# mrShark_11.net
KiCad netlist of a schematic drawn in EAGLE
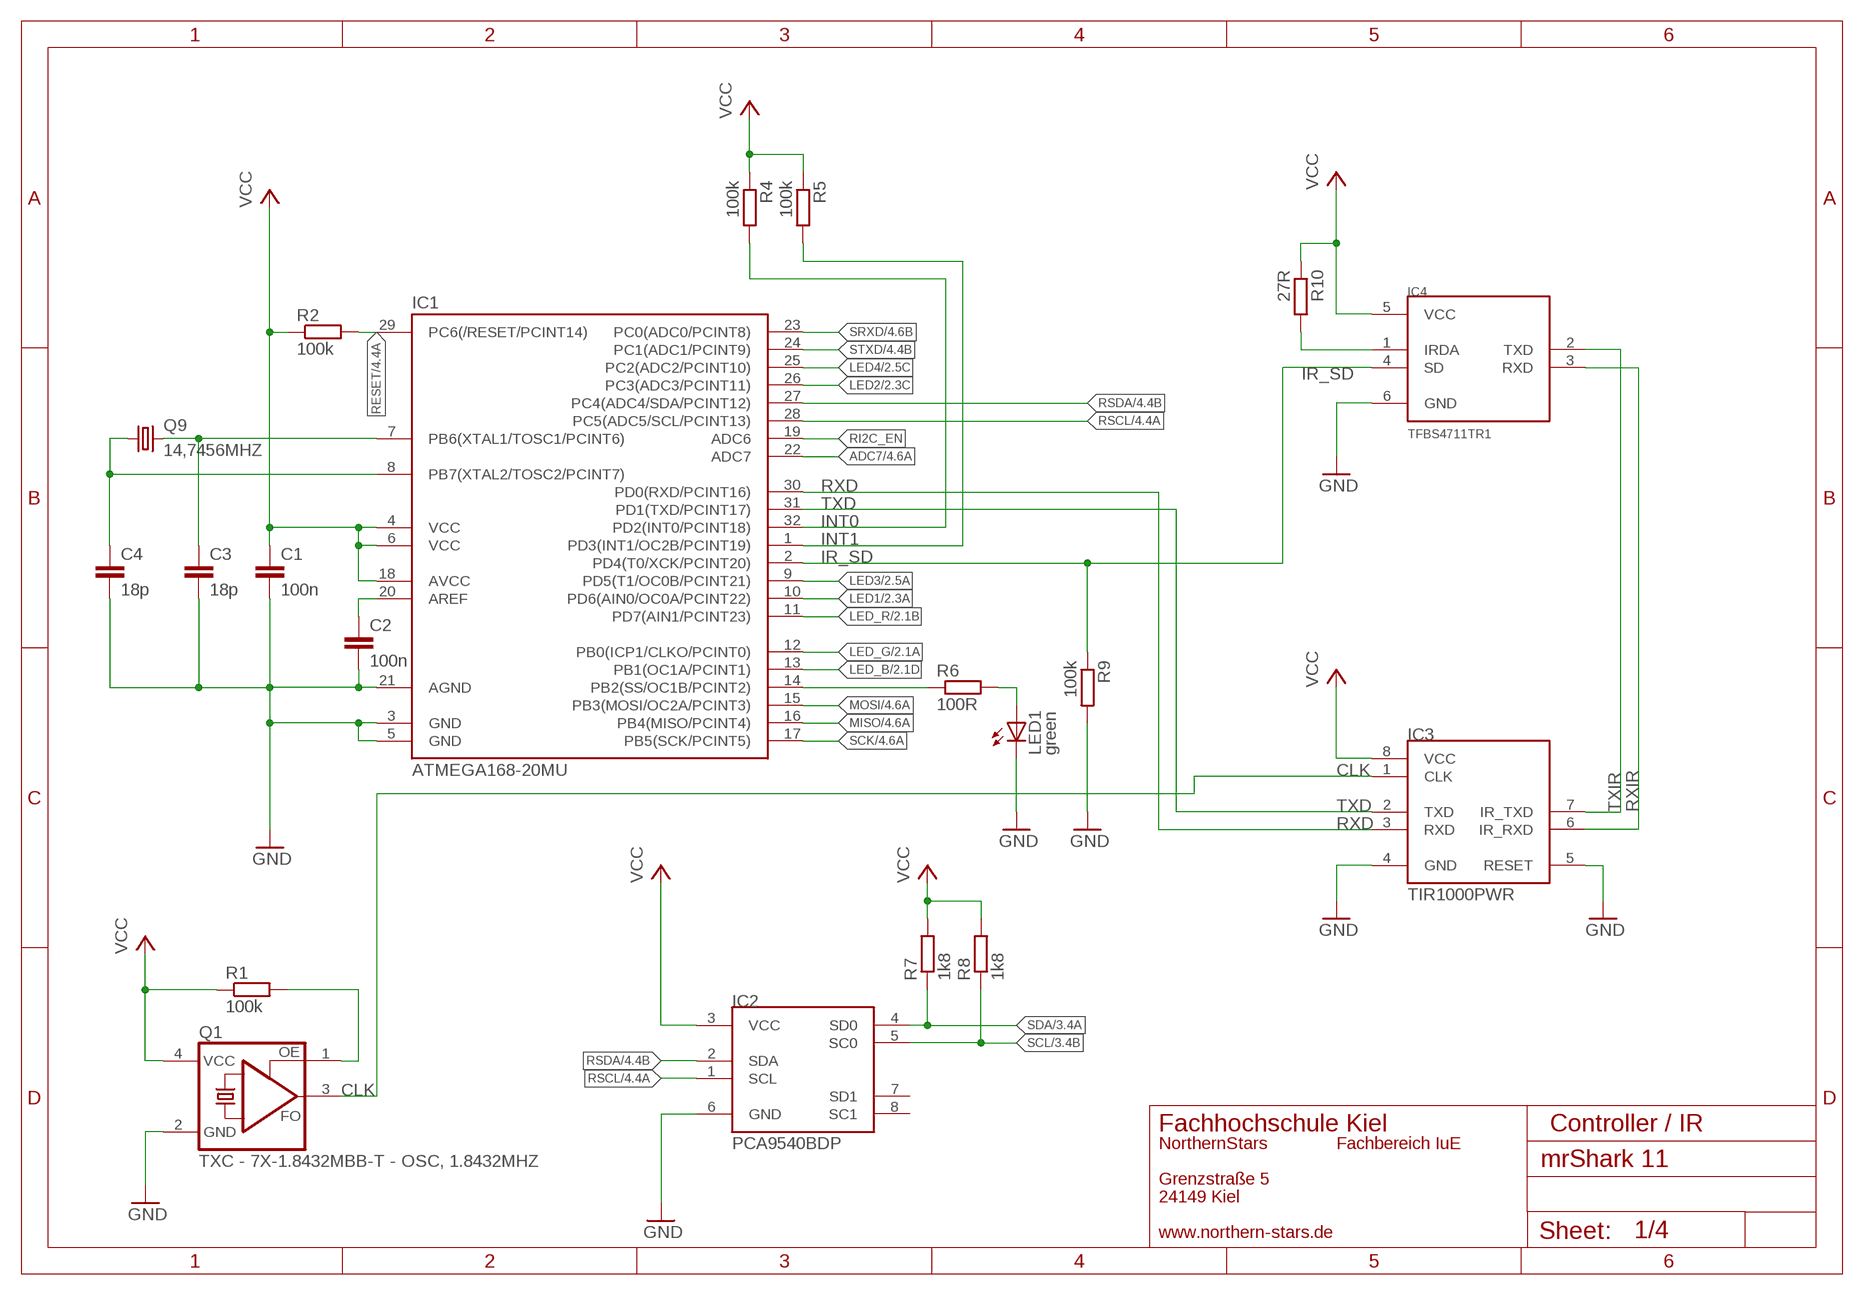
[diagram p0: schematic, sheet 1]
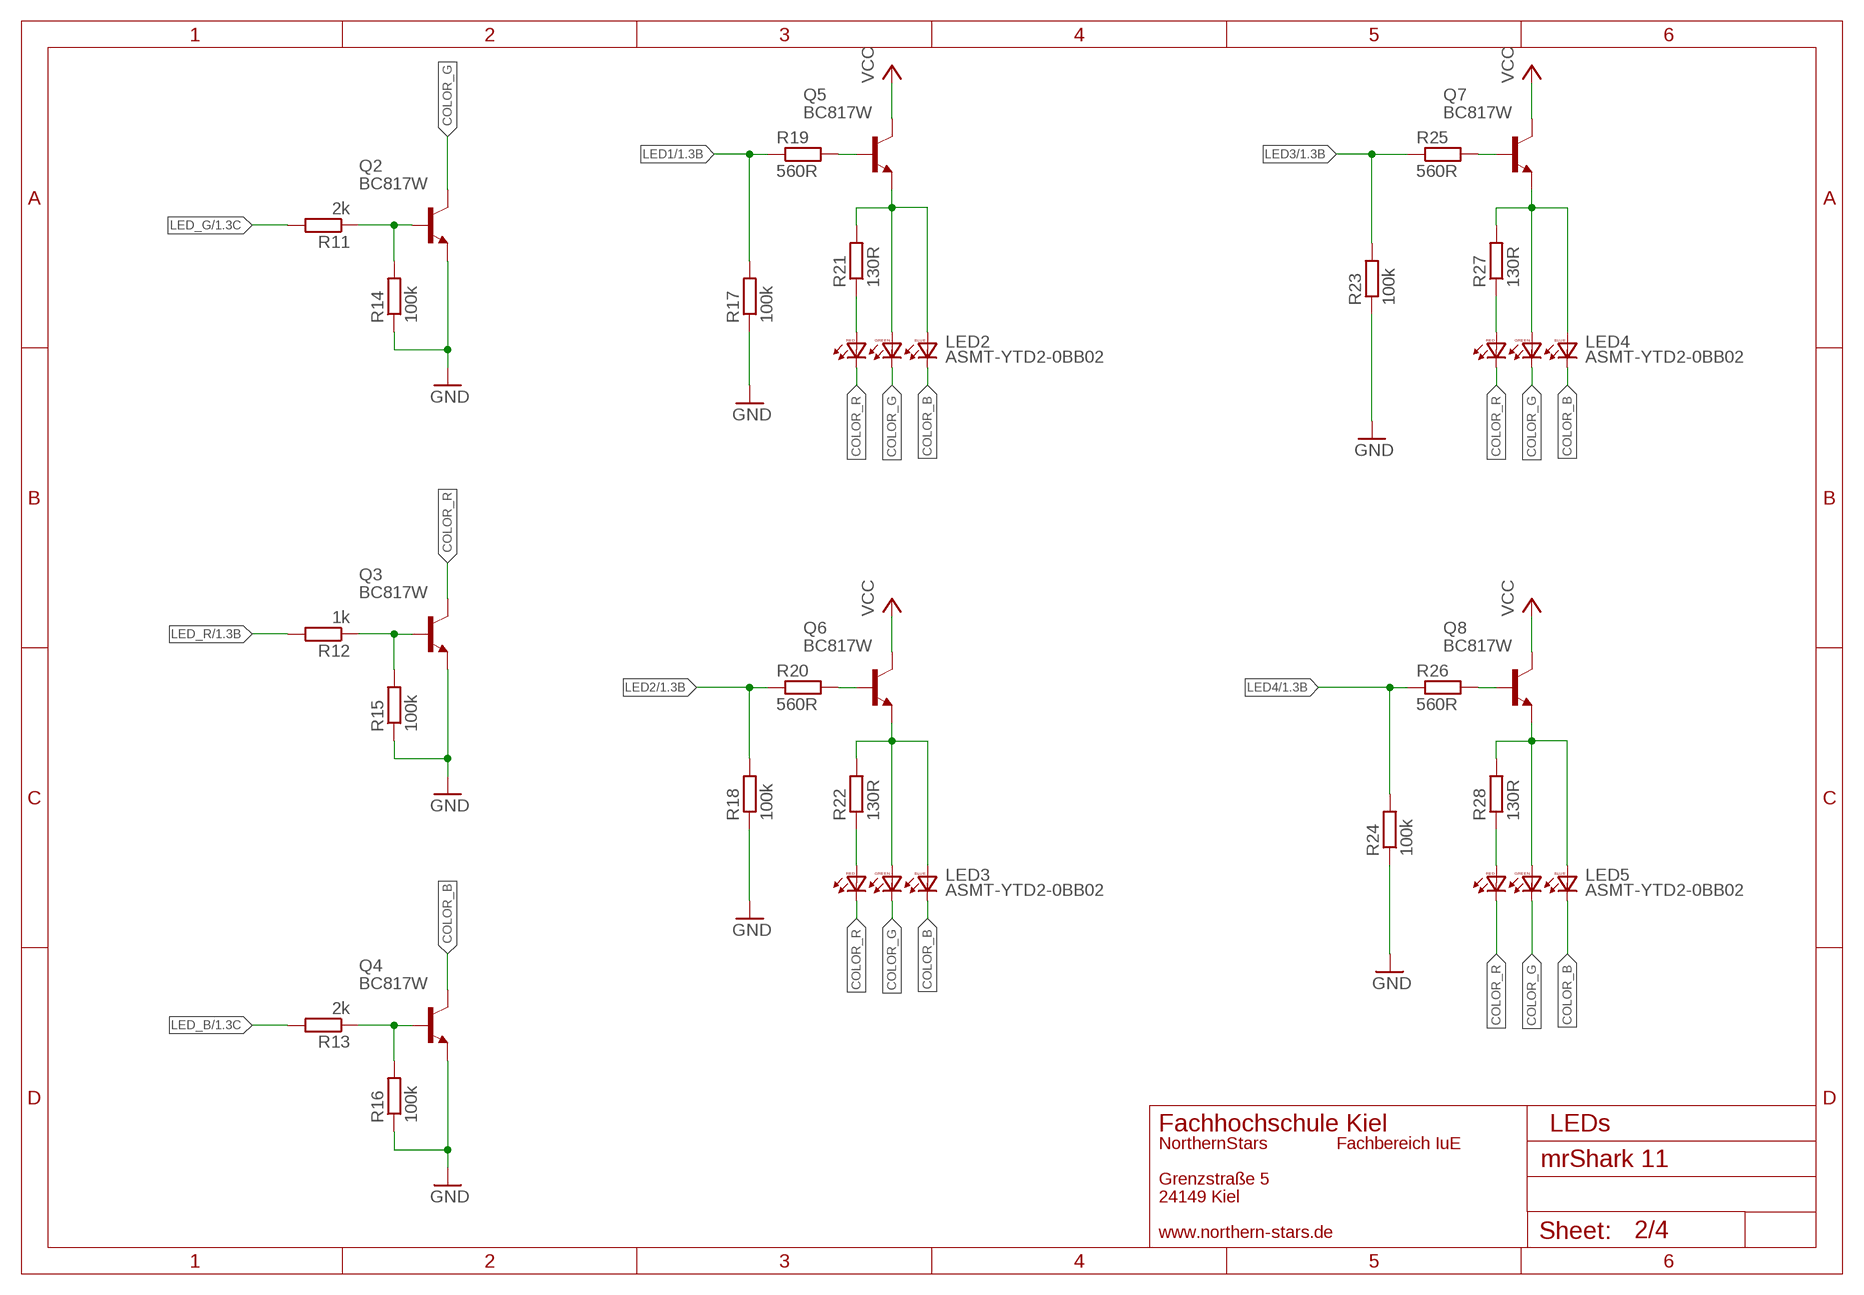
[diagram p1: schematic, sheet 2]
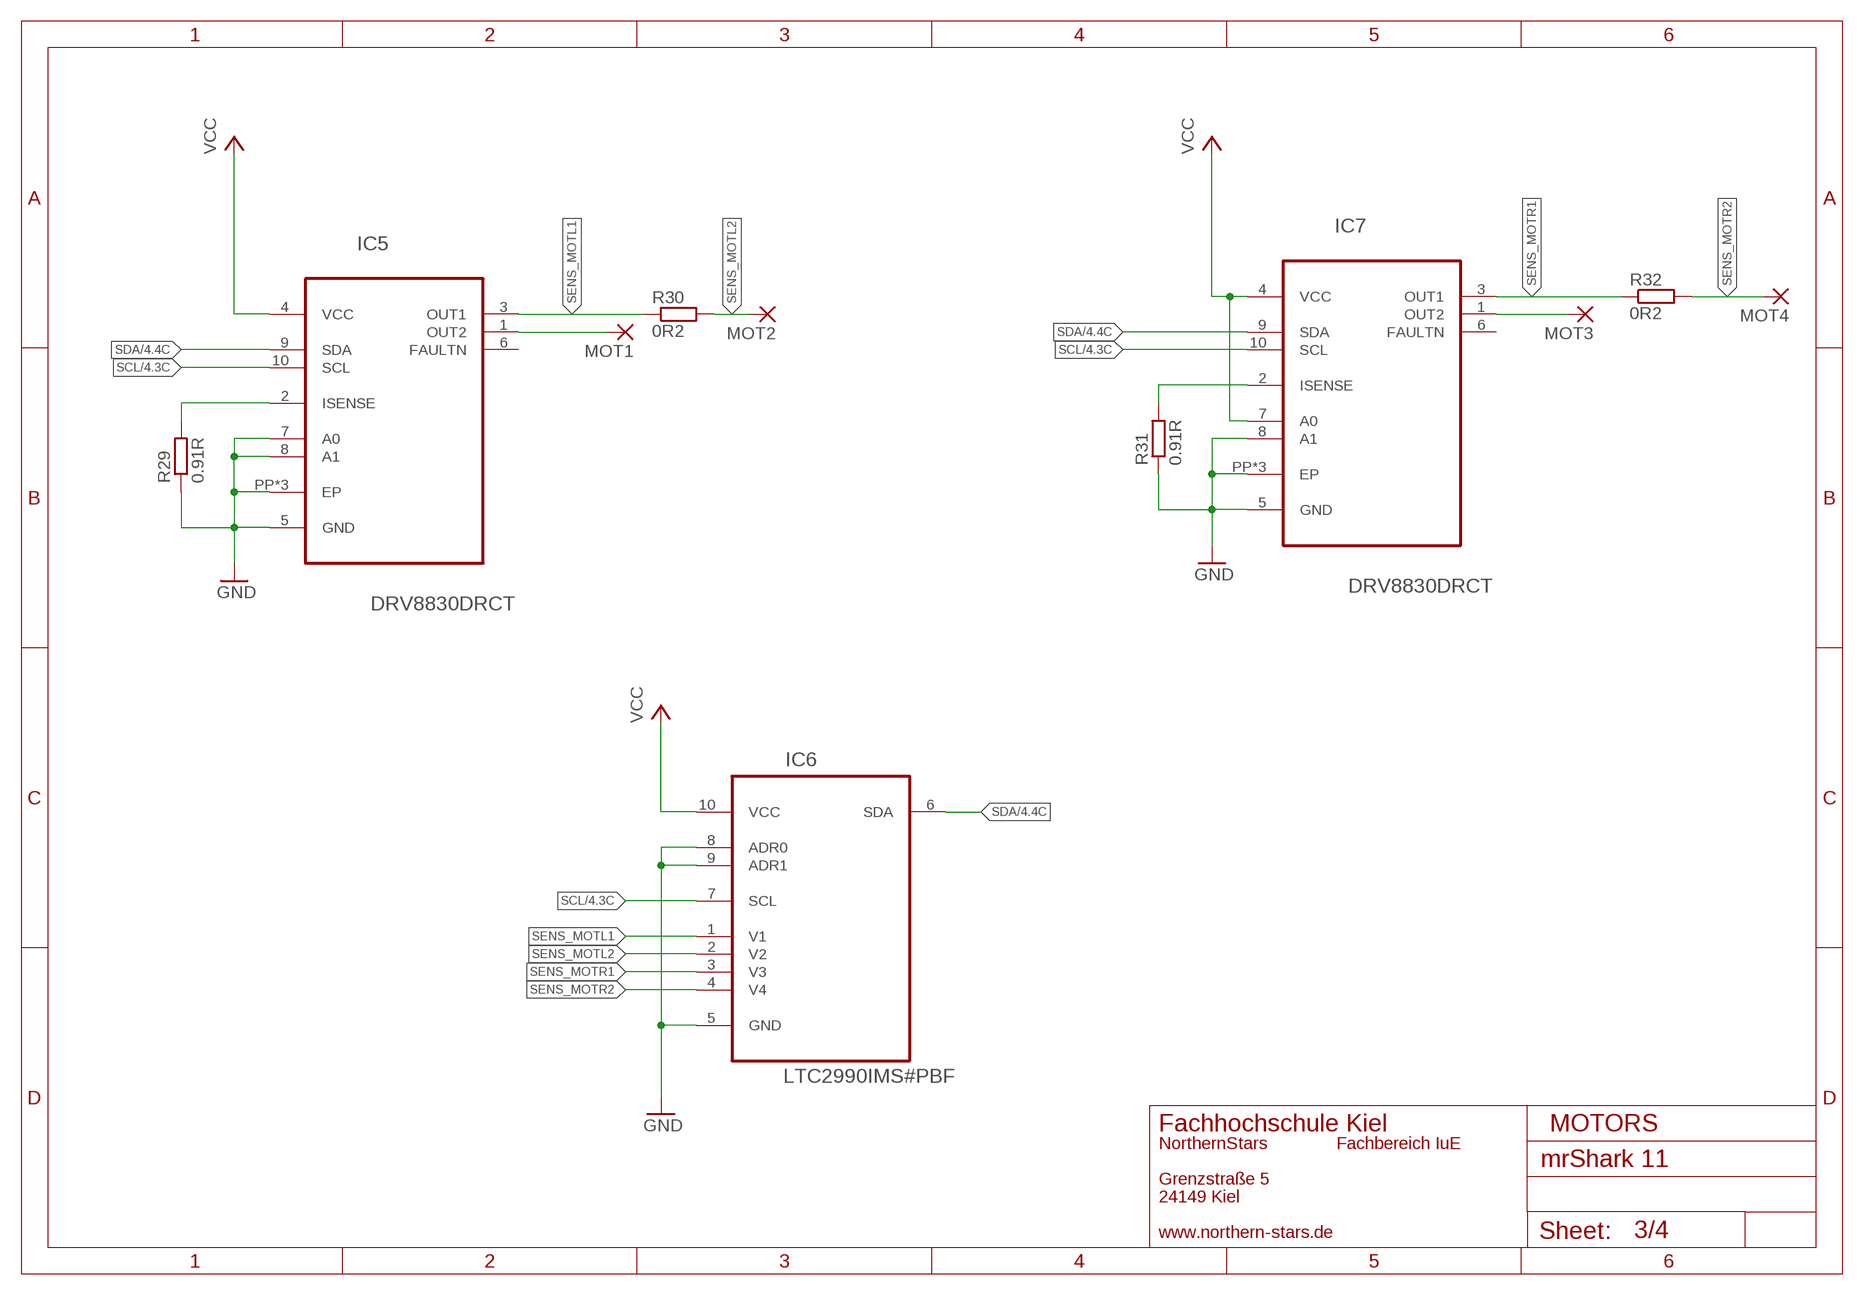
[diagram p2: schematic, sheet 3]
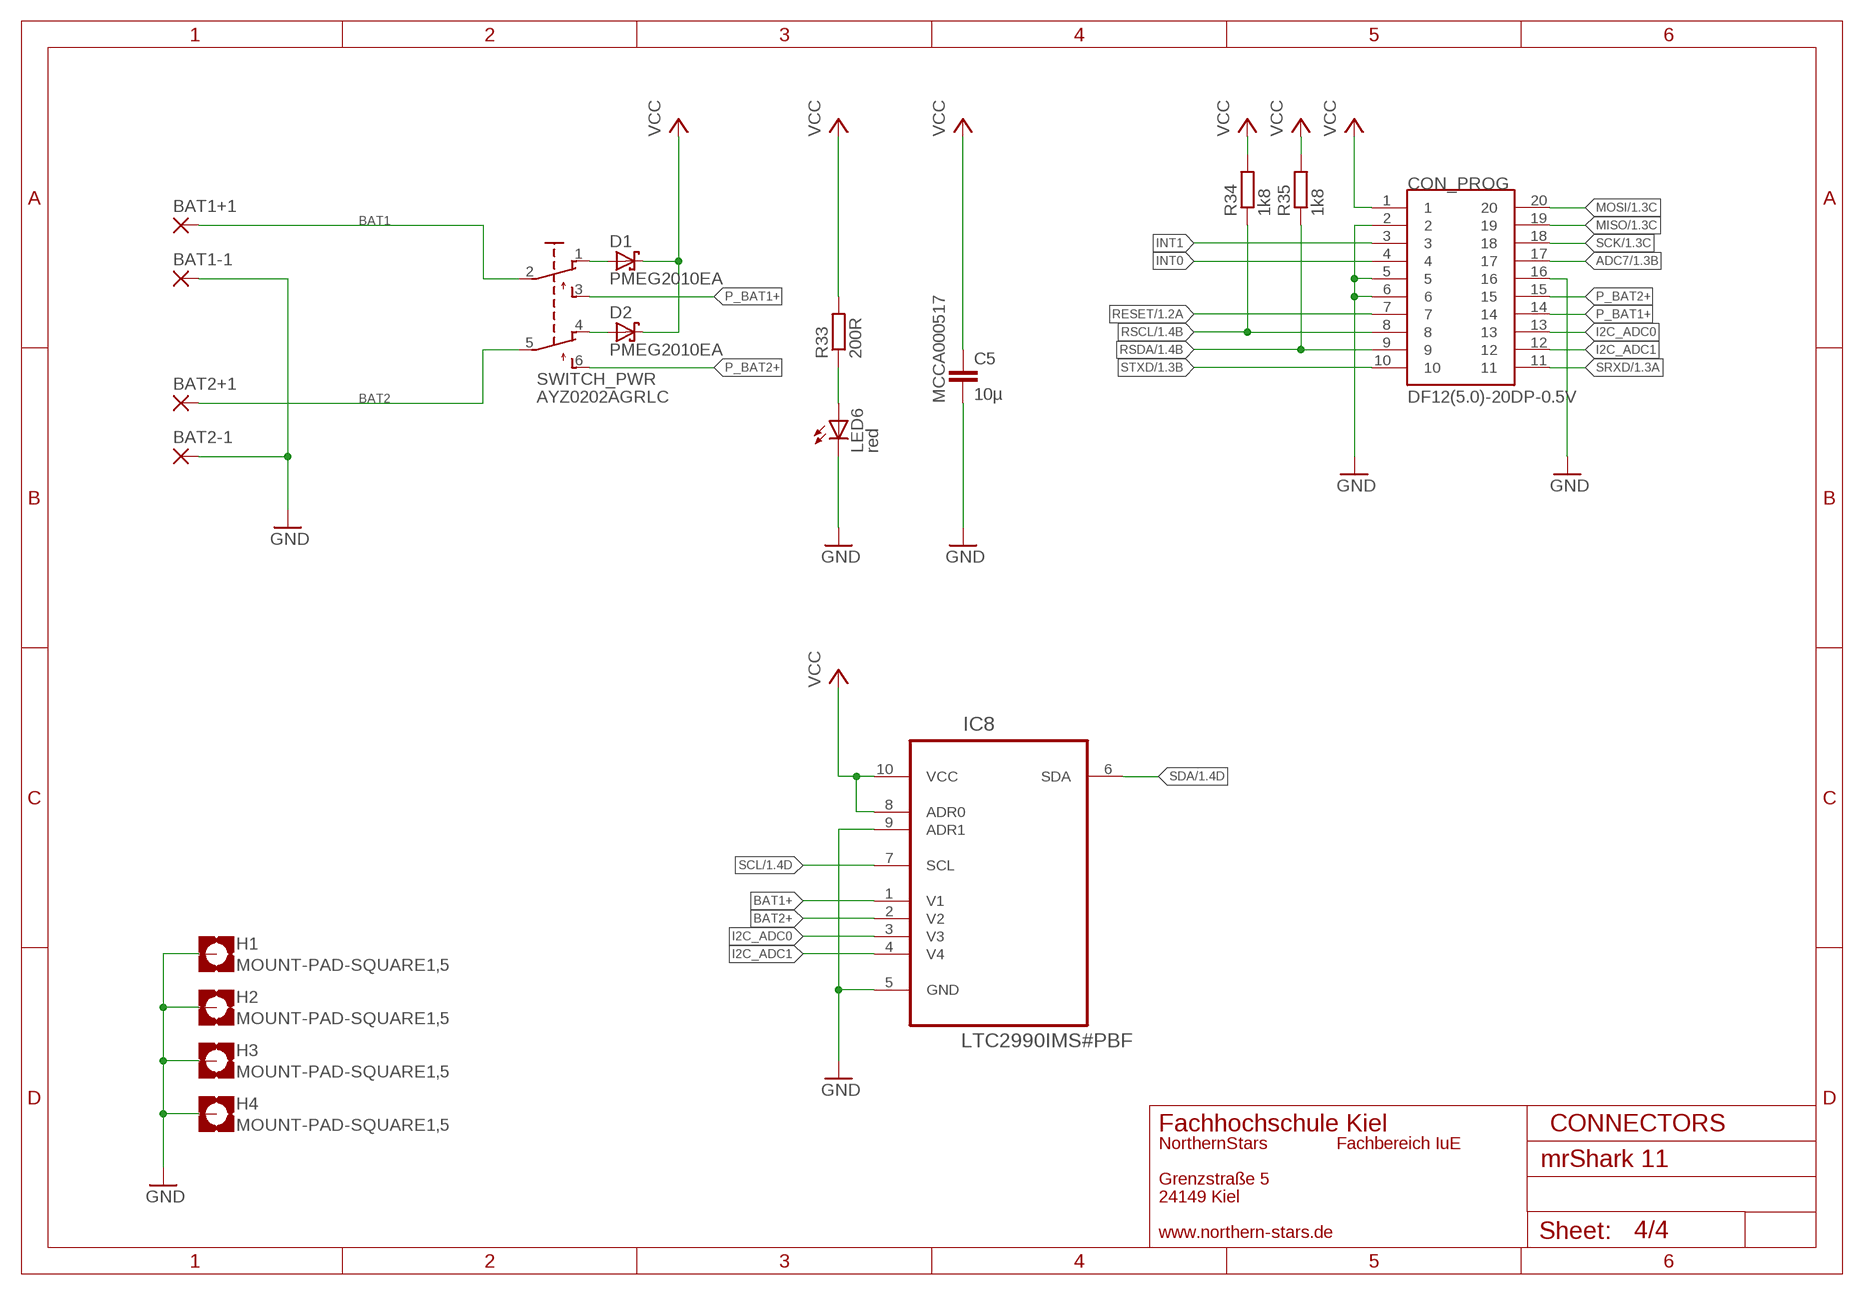
[diagram p3: schematic, sheet 4]

(export (version "E")
  (design (tool "Eeschema 10.0.6"))
  (components
    (comp (ref "IC5")
      (value "DRV8830DRCT")
      (footprint "eagle-import:S-PDSO-N10")
      (libsource (lib "eagle-import") (part "DRV8830DGQRWSON"))
    )
    (comp (ref "IC6")
      (value "LTC2990IMS#PBF")
      (footprint "eagle-import:SOP50P490X110-10N")
      (libsource (lib "eagle-import") (part "LTC2990IMSPBF"))
    )
    (comp (ref "IC7")
      (value "DRV8830DRCT")
      (footprint "eagle-import:S-PDSO-N10")
      (libsource (lib "eagle-import") (part "DRV8830DGQRWSON"))
    )
    (comp (ref "MOT1")
      (value "1,6/0,9")
      (footprint "eagle-import:1,6_0,9")
      (libsource (lib "eagle-import") (part "1,6/0,9"))
    )
    (comp (ref "MOT2")
      (value "1,6/0,9")
      (footprint "eagle-import:1,6_0,9")
      (libsource (lib "eagle-import") (part "1,6/0,9"))
    )
    (comp (ref "MOT3")
      (value "1,6/0,9")
      (footprint "eagle-import:1,6_0,9")
      (libsource (lib "eagle-import") (part "1,6/0,9"))
    )
    (comp (ref "MOT4")
      (value "1,6/0,9")
      (footprint "eagle-import:1,6_0,9")
      (libsource (lib "eagle-import") (part "1,6/0,9"))
    )
    (comp (ref "R29")
      (value "0.91R")
      (footprint "eagle-import:R0603")
      (libsource (lib "eagle-import") (part "R-EU_R0603"))
    )
    (comp (ref "R30")
      (value "0R2")
      (footprint "eagle-import:R0603")
      (libsource (lib "eagle-import") (part "R-EU_R0603"))
    )
    (comp (ref "R31")
      (value "0.91R")
      (footprint "eagle-import:R0603")
      (libsource (lib "eagle-import") (part "R-EU_R0603"))
    )
    (comp (ref "R32")
      (value "0R2")
      (footprint "eagle-import:R0603")
      (libsource (lib "eagle-import") (part "R-EU_R0603"))
    )
    (comp (ref "BAT1+1")
      (value "1,6/0,9")
      (footprint "eagle-import:1,6_0,9")
      (libsource (lib "eagle-import") (part "1,6/0,9"))
    )
    (comp (ref "BAT1-1")
      (value "1,6/0,9")
      (footprint "eagle-import:1,6_0,9")
      (libsource (lib "eagle-import") (part "1,6/0,9"))
    )
    (comp (ref "BAT2+1")
      (value "1,6/0,9")
      (footprint "eagle-import:1,6_0,9")
      (libsource (lib "eagle-import") (part "1,6/0,9"))
    )
    (comp (ref "BAT2-1")
      (value "1,6/0,9")
      (footprint "eagle-import:1,6_0,9")
      (libsource (lib "eagle-import") (part "1,6/0,9"))
    )
    (comp (ref "C5")
      (value "10µ")
      (footprint "eagle-import:C0603K")
      (libsource (lib "eagle-import") (part "C-EUC0603K"))
    )
    (comp (ref "CON_PROG")
      (value "DF12(5.0)-20DP-0.5V")
      (footprint "eagle-import:DF12-20DP")
      (libsource (lib "eagle-import") (part "DF12-20DP"))
    )
    (comp (ref "D1")
      (value "PMEG2010EA")
      (footprint "eagle-import:SOD323-R")
      (libsource (lib "eagle-import") (part "PMEG2010EAR"))
    )
    (comp (ref "D2")
      (value "PMEG2010EA")
      (footprint "eagle-import:SOD323-R")
      (libsource (lib "eagle-import") (part "PMEG2010EAR"))
    )
    (comp (ref "H1")
      (value "MOUNT-PAD-SQUARE1,5")
      (footprint "eagle-import:0,75-PAD-SQUARE")
      (libsource (lib "eagle-import") (part "MOUNT-PAD-SQUARE1,5"))
    )
    (comp (ref "H2")
      (value "MOUNT-PAD-SQUARE1,5")
      (footprint "eagle-import:0,75-PAD-SQUARE")
      (libsource (lib "eagle-import") (part "MOUNT-PAD-SQUARE1,5"))
    )
    (comp (ref "H3")
      (value "MOUNT-PAD-SQUARE1,5")
      (footprint "eagle-import:0,75-PAD-SQUARE")
      (libsource (lib "eagle-import") (part "MOUNT-PAD-SQUARE1,5"))
    )
    (comp (ref "H4")
      (value "MOUNT-PAD-SQUARE1,5")
      (footprint "eagle-import:0,75-PAD-SQUARE")
      (libsource (lib "eagle-import") (part "MOUNT-PAD-SQUARE1,5"))
    )
    (comp (ref "IC8")
      (value "LTC2990IMS#PBF")
      (footprint "eagle-import:SOP50P490X110-10N")
      (libsource (lib "eagle-import") (part "LTC2990IMSPBF"))
    )
    (comp (ref "LED6")
      (value "red")
      (footprint "eagle-import:CHIPLED_0603")
      (libsource (lib "eagle-import") (part "LEDCHIPLED_0603"))
    )
    (comp (ref "R33")
      (value "200R")
      (footprint "eagle-import:R0201")
      (libsource (lib "eagle-import") (part "R-EU_R0201"))
    )
    (comp (ref "R34")
      (value "1k8")
      (footprint "eagle-import:R0201")
      (libsource (lib "eagle-import") (part "R-EU_R0201"))
    )
    (comp (ref "R35")
      (value "1k8")
      (footprint "eagle-import:R0201")
      (libsource (lib "eagle-import") (part "R-EU_R0201"))
    )
    (comp (ref "SWITCH_PWR")
      (value "AYZ0202AGRLC")
      (footprint "eagle-import:AYZ0202AGLRC")
      (libsource (lib "eagle-import") (part "AYZ0202AGRLC"))
    )
    (comp (ref "LED2")
      (value "ASMT-YTD2-0BB02")
      (footprint "eagle-import:PLCC6K")
      (libsource (lib "eagle-import") (part "PLCC6K"))
    )
    (comp (ref "LED3")
      (value "ASMT-YTD2-0BB02")
      (footprint "eagle-import:PLCC6K")
      (libsource (lib "eagle-import") (part "PLCC6K"))
    )
    (comp (ref "LED4")
      (value "ASMT-YTD2-0BB02")
      (footprint "eagle-import:PLCC6K")
      (libsource (lib "eagle-import") (part "PLCC6K"))
    )
    (comp (ref "LED5")
      (value "ASMT-YTD2-0BB02")
      (footprint "eagle-import:PLCC6K")
      (libsource (lib "eagle-import") (part "PLCC6K"))
    )
    (comp (ref "Q2")
      (value "BC817W")
      (footprint "eagle-import:SOT323-BEC")
      (libsource (lib "eagle-import") (part "BC817W"))
    )
    (comp (ref "Q3")
      (value "BC817W")
      (footprint "eagle-import:SOT323-BEC")
      (libsource (lib "eagle-import") (part "BC817W"))
    )
    (comp (ref "Q4")
      (value "BC817W")
      (footprint "eagle-import:SOT323-BEC")
      (libsource (lib "eagle-import") (part "BC817W"))
    )
    (comp (ref "Q5")
      (value "BC817W")
      (footprint "eagle-import:SOT323-BEC")
      (libsource (lib "eagle-import") (part "BC817W"))
    )
    (comp (ref "Q6")
      (value "BC817W")
      (footprint "eagle-import:SOT323-BEC")
      (libsource (lib "eagle-import") (part "BC817W"))
    )
    (comp (ref "Q7")
      (value "BC817W")
      (footprint "eagle-import:SOT323-BEC")
      (libsource (lib "eagle-import") (part "BC817W"))
    )
    (comp (ref "Q8")
      (value "BC817W")
      (footprint "eagle-import:SOT323-BEC")
      (libsource (lib "eagle-import") (part "BC817W"))
    )
    (comp (ref "R11")
      (value "2k")
      (footprint "eagle-import:R0201")
      (libsource (lib "eagle-import") (part "R-EU_R0201"))
    )
    (comp (ref "R12")
      (value "1k")
      (footprint "eagle-import:R0201")
      (libsource (lib "eagle-import") (part "R-EU_R0201"))
    )
    (comp (ref "R13")
      (value "2k")
      (footprint "eagle-import:R0201")
      (libsource (lib "eagle-import") (part "R-EU_R0201"))
    )
    (comp (ref "R14")
      (value "100k")
      (footprint "eagle-import:R0201")
      (libsource (lib "eagle-import") (part "R-EU_R0201"))
    )
    (comp (ref "R15")
      (value "100k")
      (footprint "eagle-import:R0201")
      (libsource (lib "eagle-import") (part "R-EU_R0201"))
    )
    (comp (ref "R16")
      (value "100k")
      (footprint "eagle-import:R0201")
      (libsource (lib "eagle-import") (part "R-EU_R0201"))
    )
    (comp (ref "R17")
      (value "100k")
      (footprint "eagle-import:R0201")
      (libsource (lib "eagle-import") (part "R-EU_R0201"))
    )
    (comp (ref "R18")
      (value "100k")
      (footprint "eagle-import:R0201")
      (libsource (lib "eagle-import") (part "R-EU_R0201"))
    )
    (comp (ref "R19")
      (value "560R")
      (footprint "eagle-import:R0201")
      (libsource (lib "eagle-import") (part "R-EU_R0201"))
    )
    (comp (ref "R20")
      (value "560R")
      (footprint "eagle-import:R0201")
      (libsource (lib "eagle-import") (part "R-EU_R0201"))
    )
    (comp (ref "R21")
      (value "130R")
      (footprint "eagle-import:R0201")
      (libsource (lib "eagle-import") (part "R-EU_R0201"))
    )
    (comp (ref "R22")
      (value "130R")
      (footprint "eagle-import:R0201")
      (libsource (lib "eagle-import") (part "R-EU_R0201"))
    )
    (comp (ref "R23")
      (value "100k")
      (footprint "eagle-import:R0201")
      (libsource (lib "eagle-import") (part "R-EU_R0201"))
    )
    (comp (ref "R24")
      (value "100k")
      (footprint "eagle-import:R0201")
      (libsource (lib "eagle-import") (part "R-EU_R0201"))
    )
    (comp (ref "R25")
      (value "560R")
      (footprint "eagle-import:R0201")
      (libsource (lib "eagle-import") (part "R-EU_R0201"))
    )
    (comp (ref "R26")
      (value "560R")
      (footprint "eagle-import:R0201")
      (libsource (lib "eagle-import") (part "R-EU_R0201"))
    )
    (comp (ref "R27")
      (value "130R")
      (footprint "eagle-import:R0201")
      (libsource (lib "eagle-import") (part "R-EU_R0201"))
    )
    (comp (ref "R28")
      (value "130R")
      (footprint "eagle-import:R0201")
      (libsource (lib "eagle-import") (part "R-EU_R0201"))
    )
    (comp (ref "C1")
      (value "100n")
      (footprint "eagle-import:C0201")
      (libsource (lib "eagle-import") (part "C-EUC0201"))
    )
    (comp (ref "C2")
      (value "100n")
      (footprint "eagle-import:C0201")
      (libsource (lib "eagle-import") (part "C-EUC0201"))
    )
    (comp (ref "C3")
      (value "18p")
      (footprint "eagle-import:C0201")
      (libsource (lib "eagle-import") (part "C-EUC0201"))
    )
    (comp (ref "C4")
      (value "18p")
      (footprint "eagle-import:C0201")
      (libsource (lib "eagle-import") (part "C-EUC0201"))
    )
    (comp (ref "IC1")
      (value "ATMEGA168-20MU")
      (footprint "eagle-import:MLF32")
      (libsource (lib "eagle-import") (part "ATMEGA48/88/168-MU"))
    )
    (comp (ref "IC2")
      (value "PCA9540BDP")
      (footprint "eagle-import:TSSOP8")
      (libsource (lib "eagle-import") (part "PCA9540TSSOP8"))
    )
    (comp (ref "IC3")
      (value "TIR1000PWR")
      (footprint "eagle-import:PW_R-PDSO-G08")
      (libsource (lib "eagle-import") (part "TIR1000PWR"))
    )
    (comp (ref "IC4")
      (value "TFBS4711TR1")
      (footprint "eagle-import:TFBS4711")
      (libsource (lib "eagle-import") (part "TFBS4711TR1"))
    )
    (comp (ref "LED1")
      (value "green")
      (footprint "eagle-import:CHIPLED_0603")
      (libsource (lib "eagle-import") (part "LEDCHIPLED_0603"))
    )
    (comp (ref "Q1")
      (value "TXC - 7X-1.8432MBB-T - OSC, 1.8432MHZ")
      (footprint "eagle-import:3.2X2.5")
      (libsource (lib "eagle-import") (part "7X-SERIES"))
    )
    (comp (ref "Q9")
      (value "14,7456MHZ")
      (footprint "eagle-import:TXC_7B_SERIES")
      (libsource (lib "eagle-import") (part "TXC-7B-SERIESSMD"))
    )
    (comp (ref "R1")
      (value "100k")
      (footprint "eagle-import:R0201")
      (libsource (lib "eagle-import") (part "R-EU_R0201"))
    )
    (comp (ref "R2")
      (value "100k")
      (footprint "eagle-import:R0201")
      (libsource (lib "eagle-import") (part "R-EU_R0201"))
    )
    (comp (ref "R4")
      (value "100k")
      (footprint "eagle-import:R0201")
      (libsource (lib "eagle-import") (part "R-EU_R0201"))
    )
    (comp (ref "R5")
      (value "100k")
      (footprint "eagle-import:R0201")
      (libsource (lib "eagle-import") (part "R-EU_R0201"))
    )
    (comp (ref "R6")
      (value "100R")
      (footprint "eagle-import:R0201")
      (libsource (lib "eagle-import") (part "R-EU_R0201"))
    )
    (comp (ref "R7")
      (value "1k8")
      (footprint "eagle-import:R0201")
      (libsource (lib "eagle-import") (part "R-EU_R0201"))
    )
    (comp (ref "R8")
      (value "1k8")
      (footprint "eagle-import:R0201")
      (libsource (lib "eagle-import") (part "R-EU_R0201"))
    )
    (comp (ref "R9")
      (value "100k")
      (footprint "eagle-import:R0201")
      (libsource (lib "eagle-import") (part "R-EU_R0201"))
    )
    (comp (ref "R10")
      (value "27R")
      (footprint "eagle-import:R0201")
      (libsource (lib "eagle-import") (part "R-EU_R0201"))
    )
  )
  (nets
    (net (code "1") (name "ADC7") (class "Default")
      (node (ref "CON_PROG") (pin "17") (pinfunction "17_17") (pintype "bidirectional"))
      (node (ref "IC1") (pin "22") (pinfunction "ADC7_22") (pintype "passive"))
    )
    (net (code "2") (name "BAT1") (class "Default")
      (node (ref "BAT1+1") (pin "1") (pinfunction "P_1") (pintype "passive"))
      (node (ref "SWITCH_PWR") (pin "2") (pinfunction "P_2") (pintype "passive"))
    )
    (net (code "3") (name "BAT1+") (class "Default")
      (node (ref "D1") (pin "A") (pinfunction "A_A") (pintype "passive"))
      (node (ref "IC8") (pin "1") (pinfunction "V1_1") (pintype "input"))
      (node (ref "SWITCH_PWR") (pin "1") (pinfunction "O_1") (pintype "passive"))
    )
    (net (code "4") (name "BAT2") (class "Default")
      (node (ref "BAT2+1") (pin "1") (pinfunction "P_1") (pintype "passive"))
      (node (ref "SWITCH_PWR") (pin "5") (pinfunction "P1_5") (pintype "passive"))
    )
    (net (code "5") (name "BAT2+") (class "Default")
      (node (ref "D2") (pin "A") (pinfunction "A_A") (pintype "passive"))
      (node (ref "IC8") (pin "2") (pinfunction "V2_2") (pintype "input"))
      (node (ref "SWITCH_PWR") (pin "4") (pinfunction "O1_4") (pintype "passive"))
    )
    (net (code "6") (name "CLK") (class "Default")
      (node (ref "IC3") (pin "1") (pinfunction "CLK_1") (pintype "bidirectional"))
      (node (ref "Q1") (pin "3") (pinfunction "FO_3") (pintype "output"))
    )
    (net (code "7") (name "COLOR_B") (class "Default")
      (node (ref "LED2") (pin "1") (pinfunction "BC_1") (pintype "passive"))
      (node (ref "LED3") (pin "1") (pinfunction "BC_1") (pintype "passive"))
      (node (ref "LED4") (pin "1") (pinfunction "BC_1") (pintype "passive"))
      (node (ref "LED5") (pin "1") (pinfunction "BC_1") (pintype "passive"))
      (node (ref "Q4") (pin "C") (pinfunction "C_C") (pintype "passive"))
    )
    (net (code "8") (name "COLOR_G") (class "Default")
      (node (ref "LED2") (pin "2") (pinfunction "GC_2") (pintype "passive"))
      (node (ref "LED3") (pin "2") (pinfunction "GC_2") (pintype "passive"))
      (node (ref "LED4") (pin "2") (pinfunction "GC_2") (pintype "passive"))
      (node (ref "LED5") (pin "2") (pinfunction "GC_2") (pintype "passive"))
      (node (ref "Q2") (pin "C") (pinfunction "C_C") (pintype "passive"))
    )
    (net (code "9") (name "COLOR_R") (class "Default")
      (node (ref "LED2") (pin "3") (pinfunction "RC_3") (pintype "passive"))
      (node (ref "LED3") (pin "3") (pinfunction "RC_3") (pintype "passive"))
      (node (ref "LED4") (pin "3") (pinfunction "RC_3") (pintype "passive"))
      (node (ref "LED5") (pin "3") (pinfunction "RC_3") (pintype "passive"))
      (node (ref "Q3") (pin "C") (pinfunction "C_C") (pintype "passive"))
    )
    (net (code "10") (name "GND") (class "Default")
      (node (ref "BAT1-1") (pin "1") (pinfunction "P_1") (pintype "passive"))
      (node (ref "BAT2-1") (pin "1") (pinfunction "P_1") (pintype "passive"))
      (node (ref "C1") (pin "2") (pinfunction "2_2") (pintype "passive"))
      (node (ref "C2") (pin "2") (pinfunction "2_2") (pintype "passive"))
      (node (ref "C3") (pin "2") (pinfunction "2_2") (pintype "passive"))
      (node (ref "C4") (pin "2") (pinfunction "2_2") (pintype "passive"))
      (node (ref "C5") (pin "2") (pinfunction "2_2") (pintype "passive"))
      (node (ref "CON_PROG") (pin "16") (pinfunction "16_16") (pintype "bidirectional"))
      (node (ref "CON_PROG") (pin "2") (pinfunction "2_2") (pintype "bidirectional"))
      (node (ref "CON_PROG") (pin "5") (pinfunction "5_5") (pintype "bidirectional"))
      (node (ref "CON_PROG") (pin "6") (pinfunction "6_6") (pintype "bidirectional"))
      (node (ref "H1") (pin "P") (pinfunction "MOUNT_P") (pintype "passive"))
      (node (ref "H2") (pin "P") (pinfunction "MOUNT_P") (pintype "passive"))
      (node (ref "H3") (pin "P") (pinfunction "MOUNT_P") (pintype "passive"))
      (node (ref "H4") (pin "P") (pinfunction "MOUNT_P") (pintype "passive"))
      (node (ref "IC1") (pin "21") (pinfunction "AGND_21") (pintype "power_in"))
      (node (ref "IC1") (pin "3") (pinfunction "GND_3") (pintype "power_in"))
      (node (ref "IC1") (pin "5") (pinfunction "GND_5") (pintype "power_in"))
      (node (ref "IC2") (pin "6") (pinfunction "GND_6") (pintype "bidirectional"))
      (node (ref "IC3") (pin "4") (pinfunction "GND_4") (pintype "bidirectional"))
      (node (ref "IC3") (pin "5") (pinfunction "RESET_5") (pintype "bidirectional"))
      (node (ref "IC4") (pin "6") (pinfunction "GND_6") (pintype "bidirectional"))
      (node (ref "IC5") (pin "5") (pinfunction "GND_5") (pintype "passive"))
      (node (ref "IC5") (pin "7") (pinfunction "A0_7") (pintype "input"))
      (node (ref "IC5") (pin "8") (pinfunction "A1_8") (pintype "input"))
      (node (ref "IC5") (pin "PP") (pinfunction "EP_PP") (pintype "passive"))
      (node (ref "IC5") (pin "PP@1") (pinfunction "EP_PP@1") (pintype "passive"))
      (node (ref "IC5") (pin "PP@2") (pinfunction "EP_PP@2") (pintype "passive"))
      (node (ref "IC6") (pin "5") (pinfunction "GND_5") (pintype "passive"))
      (node (ref "IC6") (pin "8") (pinfunction "ADR0_8") (pintype "input"))
      (node (ref "IC6") (pin "9") (pinfunction "ADR1_9") (pintype "input"))
      (node (ref "IC7") (pin "5") (pinfunction "GND_5") (pintype "passive"))
      (node (ref "IC7") (pin "8") (pinfunction "A1_8") (pintype "input"))
      (node (ref "IC7") (pin "PP") (pinfunction "EP_PP") (pintype "passive"))
      (node (ref "IC7") (pin "PP@1") (pinfunction "EP_PP@1") (pintype "passive"))
      (node (ref "IC7") (pin "PP@2") (pinfunction "EP_PP@2") (pintype "passive"))
      (node (ref "IC8") (pin "5") (pinfunction "GND_5") (pintype "passive"))
      (node (ref "IC8") (pin "9") (pinfunction "ADR1_9") (pintype "input"))
      (node (ref "LED1") (pin "C") (pinfunction "C_C") (pintype "passive"))
      (node (ref "LED6") (pin "C") (pinfunction "C_C") (pintype "passive"))
      (node (ref "Q1") (pin "2") (pinfunction "GND_2") (pintype "power_in"))
      (node (ref "Q2") (pin "E") (pinfunction "E_E") (pintype "passive"))
      (node (ref "Q3") (pin "E") (pinfunction "E_E") (pintype "passive"))
      (node (ref "Q4") (pin "E") (pinfunction "E_E") (pintype "passive"))
      (node (ref "R14") (pin "1") (pinfunction "1_1") (pintype "passive"))
      (node (ref "R15") (pin "1") (pinfunction "1_1") (pintype "passive"))
      (node (ref "R16") (pin "1") (pinfunction "1_1") (pintype "passive"))
      (node (ref "R17") (pin "1") (pinfunction "1_1") (pintype "passive"))
      (node (ref "R18") (pin "1") (pinfunction "1_1") (pintype "passive"))
      (node (ref "R23") (pin "1") (pinfunction "1_1") (pintype "passive"))
      (node (ref "R24") (pin "1") (pinfunction "1_1") (pintype "passive"))
      (node (ref "R29") (pin "1") (pinfunction "1_1") (pintype "passive"))
      (node (ref "R31") (pin "1") (pinfunction "1_1") (pintype "passive"))
      (node (ref "R9") (pin "2") (pinfunction "2_2") (pintype "passive"))
    )
    (net (code "11") (name "I2C_ADC0") (class "Default")
      (node (ref "CON_PROG") (pin "13") (pinfunction "13_13") (pintype "bidirectional"))
      (node (ref "IC8") (pin "3") (pinfunction "V3_3") (pintype "input"))
    )
    (net (code "12") (name "I2C_ADC1") (class "Default")
      (node (ref "CON_PROG") (pin "12") (pinfunction "12_12") (pintype "bidirectional"))
      (node (ref "IC8") (pin "4") (pinfunction "V4_4") (pintype "input"))
    )
    (net (code "13") (name "INT0") (class "Default")
      (node (ref "CON_PROG") (pin "4") (pinfunction "4_4") (pintype "bidirectional"))
      (node (ref "IC1") (pin "32") (pinfunction "PD2(INT0/PCINT18)_32") (pintype "bidirectional"))
      (node (ref "R4") (pin "2") (pinfunction "2_2") (pintype "passive"))
    )
    (net (code "14") (name "INT1") (class "Default")
      (node (ref "CON_PROG") (pin "3") (pinfunction "3_3") (pintype "bidirectional"))
      (node (ref "IC1") (pin "1") (pinfunction "PD3(INT1/OC2B/PCINT19)_1") (pintype "bidirectional"))
      (node (ref "R5") (pin "2") (pinfunction "2_2") (pintype "passive"))
    )
    (net (code "15") (name "IR_SD") (class "Default")
      (node (ref "IC1") (pin "2") (pinfunction "PD4(T0/XCK/PCINT20)_2") (pintype "bidirectional"))
      (node (ref "IC4") (pin "4") (pinfunction "SD_4") (pintype "bidirectional"))
      (node (ref "R9") (pin "1") (pinfunction "1_1") (pintype "passive"))
    )
    (net (code "16") (name "LED1") (class "Default")
      (node (ref "IC1") (pin "10") (pinfunction "PD6(AIN0/OC0A/PCINT22)_10") (pintype "bidirectional"))
      (node (ref "R17") (pin "2") (pinfunction "2_2") (pintype "passive"))
      (node (ref "R19") (pin "1") (pinfunction "1_1") (pintype "passive"))
    )
    (net (code "17") (name "LED2") (class "Default")
      (node (ref "IC1") (pin "26") (pinfunction "PC3(ADC3/PCINT11)_26") (pintype "bidirectional"))
      (node (ref "R18") (pin "2") (pinfunction "2_2") (pintype "passive"))
      (node (ref "R20") (pin "1") (pinfunction "1_1") (pintype "passive"))
    )
    (net (code "18") (name "LED3") (class "Default")
      (node (ref "IC1") (pin "9") (pinfunction "PD5(T1/OC0B/PCINT21)_9") (pintype "bidirectional"))
      (node (ref "R23") (pin "2") (pinfunction "2_2") (pintype "passive"))
      (node (ref "R25") (pin "1") (pinfunction "1_1") (pintype "passive"))
    )
    (net (code "19") (name "LED4") (class "Default")
      (node (ref "IC1") (pin "25") (pinfunction "PC2(ADC2/PCINT10)_25") (pintype "bidirectional"))
      (node (ref "R24") (pin "2") (pinfunction "2_2") (pintype "passive"))
      (node (ref "R26") (pin "1") (pinfunction "1_1") (pintype "passive"))
    )
    (net (code "20") (name "LED_B") (class "Default")
      (node (ref "IC1") (pin "13") (pinfunction "PB1(OC1A/PCINT1)_13") (pintype "bidirectional"))
      (node (ref "R13") (pin "2") (pinfunction "2_2") (pintype "passive"))
    )
    (net (code "21") (name "LED_G") (class "Default")
      (node (ref "IC1") (pin "12") (pinfunction "PB0(ICP1/CLKO/PCINT0)_12") (pintype "bidirectional"))
      (node (ref "R11") (pin "2") (pinfunction "2_2") (pintype "passive"))
    )
    (net (code "22") (name "LED_R") (class "Default")
      (node (ref "IC1") (pin "11") (pinfunction "PD7(AIN1/PCINT23)_11") (pintype "bidirectional"))
      (node (ref "R12") (pin "2") (pinfunction "2_2") (pintype "passive"))
    )
    (net (code "23") (name "MISO") (class "Default")
      (node (ref "CON_PROG") (pin "19") (pinfunction "19_19") (pintype "bidirectional"))
      (node (ref "IC1") (pin "16") (pinfunction "PB4(MISO/PCINT4)_16") (pintype "bidirectional"))
    )
    (net (code "24") (name "MOSI") (class "Default")
      (node (ref "CON_PROG") (pin "20") (pinfunction "20_20") (pintype "bidirectional"))
      (node (ref "IC1") (pin "15") (pinfunction "PB3(MOSI/OC2A/PCINT3)_15") (pintype "bidirectional"))
    )
    (net (code "25") (name "Net-(IC1-AREF)") (class "Default")
      (node (ref "C2") (pin "1") (pinfunction "1_1") (pintype "passive"))
      (node (ref "IC1") (pin "20") (pinfunction "AREF_20") (pintype "passive"))
    )
    (net (code "26") (name "Net-(IC1-PB2(SS{slash}OC1B{slash}PCINT2))") (class "Default")
      (node (ref "IC1") (pin "14") (pinfunction "PB2(SS/OC1B/PCINT2)_14") (pintype "bidirectional"))
      (node (ref "R6") (pin "1") (pinfunction "1_1") (pintype "passive"))
    )
    (net (code "27") (name "Net-(IC1-PB6(XTAL1{slash}TOSC1{slash}PCINT6))") (class "Default")
      (node (ref "C3") (pin "1") (pinfunction "1_1") (pintype "passive"))
      (node (ref "IC1") (pin "7") (pinfunction "PB6(XTAL1/TOSC1/PCINT6)_7") (pintype "bidirectional"))
      (node (ref "Q9") (pin "3") (pinfunction "2_3") (pintype "passive"))
    )
    (net (code "28") (name "Net-(IC1-PB7(XTAL2{slash}TOSC2{slash}PCINT7))") (class "Default")
      (node (ref "C4") (pin "1") (pinfunction "1_1") (pintype "passive"))
      (node (ref "IC1") (pin "8") (pinfunction "PB7(XTAL2/TOSC2/PCINT7)_8") (pintype "bidirectional"))
      (node (ref "Q9") (pin "1") (pinfunction "1_1") (pintype "passive"))
    )
    (net (code "29") (name "Net-(IC4-IRDA)") (class "Default")
      (node (ref "IC4") (pin "1") (pinfunction "IRDA_1") (pintype "bidirectional"))
      (node (ref "R10") (pin "2") (pinfunction "2_2") (pintype "passive"))
    )
    (net (code "30") (name "Net-(IC5-ISENSE)") (class "Default")
      (node (ref "IC5") (pin "2") (pinfunction "ISENSE_2") (pintype "input"))
      (node (ref "R29") (pin "2") (pinfunction "2_2") (pintype "passive"))
    )
    (net (code "31") (name "Net-(IC5-OUT2)") (class "Default")
      (node (ref "IC5") (pin "1") (pinfunction "OUT2_1") (pintype "output"))
      (node (ref "MOT1") (pin "1") (pinfunction "P_1") (pintype "passive"))
    )
    (net (code "32") (name "Net-(IC7-ISENSE)") (class "Default")
      (node (ref "IC7") (pin "2") (pinfunction "ISENSE_2") (pintype "input"))
      (node (ref "R31") (pin "2") (pinfunction "2_2") (pintype "passive"))
    )
    (net (code "33") (name "Net-(IC7-OUT2)") (class "Default")
      (node (ref "IC7") (pin "1") (pinfunction "OUT2_1") (pintype "output"))
      (node (ref "MOT3") (pin "1") (pinfunction "P_1") (pintype "passive"))
    )
    (net (code "34") (name "Net-(LED1-PadA)") (class "Default")
      (node (ref "LED1") (pin "A") (pinfunction "A_A") (pintype "passive"))
      (node (ref "R6") (pin "2") (pinfunction "2_2") (pintype "passive"))
    )
    (net (code "35") (name "Net-(LED2-BA)") (class "Default")
      (node (ref "LED2") (pin "5") (pinfunction "GA_5") (pintype "passive"))
      (node (ref "LED2") (pin "6") (pinfunction "BA_6") (pintype "passive"))
      (node (ref "Q5") (pin "E") (pinfunction "E_E") (pintype "passive"))
      (node (ref "R21") (pin "2") (pinfunction "2_2") (pintype "passive"))
    )
    (net (code "36") (name "Net-(LED2-RA)") (class "Default")
      (node (ref "LED2") (pin "4") (pinfunction "RA_4") (pintype "passive"))
      (node (ref "R21") (pin "1") (pinfunction "1_1") (pintype "passive"))
    )
    (net (code "37") (name "Net-(LED3-BA)") (class "Default")
      (node (ref "LED3") (pin "5") (pinfunction "GA_5") (pintype "passive"))
      (node (ref "LED3") (pin "6") (pinfunction "BA_6") (pintype "passive"))
      (node (ref "Q6") (pin "E") (pinfunction "E_E") (pintype "passive"))
      (node (ref "R22") (pin "2") (pinfunction "2_2") (pintype "passive"))
    )
    (net (code "38") (name "Net-(LED3-RA)") (class "Default")
      (node (ref "LED3") (pin "4") (pinfunction "RA_4") (pintype "passive"))
      (node (ref "R22") (pin "1") (pinfunction "1_1") (pintype "passive"))
    )
    (net (code "39") (name "Net-(LED4-BA)") (class "Default")
      (node (ref "LED4") (pin "5") (pinfunction "GA_5") (pintype "passive"))
      (node (ref "LED4") (pin "6") (pinfunction "BA_6") (pintype "passive"))
      (node (ref "Q7") (pin "E") (pinfunction "E_E") (pintype "passive"))
      (node (ref "R27") (pin "2") (pinfunction "2_2") (pintype "passive"))
    )
    (net (code "40") (name "Net-(LED4-RA)") (class "Default")
      (node (ref "LED4") (pin "4") (pinfunction "RA_4") (pintype "passive"))
      (node (ref "R27") (pin "1") (pinfunction "1_1") (pintype "passive"))
    )
    (net (code "41") (name "Net-(LED5-BA)") (class "Default")
      (node (ref "LED5") (pin "5") (pinfunction "GA_5") (pintype "passive"))
      (node (ref "LED5") (pin "6") (pinfunction "BA_6") (pintype "passive"))
      (node (ref "Q8") (pin "E") (pinfunction "E_E") (pintype "passive"))
      (node (ref "R28") (pin "2") (pinfunction "2_2") (pintype "passive"))
    )
    (net (code "42") (name "Net-(LED5-RA)") (class "Default")
      (node (ref "LED5") (pin "4") (pinfunction "RA_4") (pintype "passive"))
      (node (ref "R28") (pin "1") (pinfunction "1_1") (pintype "passive"))
    )
    (net (code "43") (name "Net-(LED6-PadA)") (class "Default")
      (node (ref "LED6") (pin "A") (pinfunction "A_A") (pintype "passive"))
      (node (ref "R33") (pin "1") (pinfunction "1_1") (pintype "passive"))
    )
    (net (code "44") (name "Net-(Q1-OE)") (class "Default")
      (node (ref "Q1") (pin "1") (pinfunction "OE_1") (pintype "input"))
      (node (ref "R1") (pin "2") (pinfunction "2_2") (pintype "passive"))
    )
    (net (code "45") (name "Net-(Q2-PadB)") (class "Default")
      (node (ref "Q2") (pin "B") (pinfunction "B_B") (pintype "passive"))
      (node (ref "R11") (pin "1") (pinfunction "1_1") (pintype "passive"))
      (node (ref "R14") (pin "2") (pinfunction "2_2") (pintype "passive"))
    )
    (net (code "46") (name "Net-(Q3-PadB)") (class "Default")
      (node (ref "Q3") (pin "B") (pinfunction "B_B") (pintype "passive"))
      (node (ref "R12") (pin "1") (pinfunction "1_1") (pintype "passive"))
      (node (ref "R15") (pin "2") (pinfunction "2_2") (pintype "passive"))
    )
    (net (code "47") (name "Net-(Q4-PadB)") (class "Default")
      (node (ref "Q4") (pin "B") (pinfunction "B_B") (pintype "passive"))
      (node (ref "R13") (pin "1") (pinfunction "1_1") (pintype "passive"))
      (node (ref "R16") (pin "2") (pinfunction "2_2") (pintype "passive"))
    )
    (net (code "48") (name "Net-(Q5-PadB)") (class "Default")
      (node (ref "Q5") (pin "B") (pinfunction "B_B") (pintype "passive"))
      (node (ref "R19") (pin "2") (pinfunction "2_2") (pintype "passive"))
    )
    (net (code "49") (name "Net-(Q6-PadB)") (class "Default")
      (node (ref "Q6") (pin "B") (pinfunction "B_B") (pintype "passive"))
      (node (ref "R20") (pin "2") (pinfunction "2_2") (pintype "passive"))
    )
    (net (code "50") (name "Net-(Q7-PadB)") (class "Default")
      (node (ref "Q7") (pin "B") (pinfunction "B_B") (pintype "passive"))
      (node (ref "R25") (pin "2") (pinfunction "2_2") (pintype "passive"))
    )
    (net (code "51") (name "Net-(Q8-PadB)") (class "Default")
      (node (ref "Q8") (pin "B") (pinfunction "B_B") (pintype "passive"))
      (node (ref "R26") (pin "2") (pinfunction "2_2") (pintype "passive"))
    )
    (net (code "52") (name "P_BAT1+") (class "Default")
      (node (ref "CON_PROG") (pin "14") (pinfunction "14_14") (pintype "bidirectional"))
      (node (ref "SWITCH_PWR") (pin "3") (pinfunction "S_3") (pintype "passive"))
    )
    (net (code "53") (name "P_BAT2+") (class "Default")
      (node (ref "CON_PROG") (pin "15") (pinfunction "15_15") (pintype "bidirectional"))
      (node (ref "SWITCH_PWR") (pin "6") (pinfunction "S1_6") (pintype "passive"))
    )
    (net (code "54") (name "RESET") (class "Default")
      (node (ref "CON_PROG") (pin "7") (pinfunction "7_7") (pintype "bidirectional"))
      (node (ref "IC1") (pin "29") (pinfunction "PC6(/RESET/PCINT14)_29") (pintype "bidirectional"))
      (node (ref "R2") (pin "2") (pinfunction "2_2") (pintype "passive"))
    )
    (net (code "55") (name "RI2C_EN") (class "Default")
      (node (ref "IC1") (pin "19") (pinfunction "ADC6_19") (pintype "passive"))
    )
    (net (code "56") (name "RSCL") (class "Default")
      (node (ref "CON_PROG") (pin "8") (pinfunction "8_8") (pintype "bidirectional"))
      (node (ref "IC1") (pin "28") (pinfunction "PC5(ADC5/SCL/PCINT13)_28") (pintype "bidirectional"))
      (node (ref "IC2") (pin "1") (pinfunction "SCL_1") (pintype "bidirectional"))
      (node (ref "R34") (pin "1") (pinfunction "1_1") (pintype "passive"))
    )
    (net (code "57") (name "RSDA") (class "Default")
      (node (ref "CON_PROG") (pin "9") (pinfunction "9_9") (pintype "bidirectional"))
      (node (ref "IC1") (pin "27") (pinfunction "PC4(ADC4/SDA/PCINT12)_27") (pintype "bidirectional"))
      (node (ref "IC2") (pin "2") (pinfunction "SDA_2") (pintype "bidirectional"))
      (node (ref "R35") (pin "1") (pinfunction "1_1") (pintype "passive"))
    )
    (net (code "58") (name "RXD") (class "Default")
      (node (ref "IC1") (pin "30") (pinfunction "PD0(RXD/PCINT16)_30") (pintype "bidirectional"))
      (node (ref "IC3") (pin "3") (pinfunction "RXD_3") (pintype "bidirectional"))
    )
    (net (code "59") (name "RXIR") (class "Default")
      (node (ref "IC3") (pin "6") (pinfunction "IR_RXD_6") (pintype "bidirectional"))
      (node (ref "IC4") (pin "3") (pinfunction "RXD_3") (pintype "output"))
    )
    (net (code "60") (name "SCK") (class "Default")
      (node (ref "CON_PROG") (pin "18") (pinfunction "18_18") (pintype "bidirectional"))
      (node (ref "IC1") (pin "17") (pinfunction "PB5(SCK/PCINT5)_17") (pintype "bidirectional"))
    )
    (net (code "61") (name "SCL") (class "Default")
      (node (ref "IC2") (pin "5") (pinfunction "SC0_5") (pintype "bidirectional"))
      (node (ref "IC5") (pin "10") (pinfunction "SCL_10") (pintype "input"))
      (node (ref "IC6") (pin "7") (pinfunction "SCL_7") (pintype "input"))
      (node (ref "IC7") (pin "10") (pinfunction "SCL_10") (pintype "input"))
      (node (ref "IC8") (pin "7") (pinfunction "SCL_7") (pintype "input"))
      (node (ref "R8") (pin "1") (pinfunction "1_1") (pintype "passive"))
    )
    (net (code "62") (name "SDA") (class "Default")
      (node (ref "IC2") (pin "4") (pinfunction "SD0_4") (pintype "bidirectional"))
      (node (ref "IC5") (pin "9") (pinfunction "SDA_9") (pintype "bidirectional"))
      (node (ref "IC6") (pin "6") (pinfunction "SDA_6") (pintype "bidirectional"))
      (node (ref "IC7") (pin "9") (pinfunction "SDA_9") (pintype "bidirectional"))
      (node (ref "IC8") (pin "6") (pinfunction "SDA_6") (pintype "bidirectional"))
      (node (ref "R7") (pin "1") (pinfunction "1_1") (pintype "passive"))
    )
    (net (code "63") (name "SENS_MOTL1") (class "Default")
      (node (ref "IC5") (pin "3") (pinfunction "OUT1_3") (pintype "output"))
      (node (ref "IC6") (pin "1") (pinfunction "V1_1") (pintype "input"))
      (node (ref "R30") (pin "1") (pinfunction "1_1") (pintype "passive"))
    )
    (net (code "64") (name "SENS_MOTL2") (class "Default")
      (node (ref "IC6") (pin "2") (pinfunction "V2_2") (pintype "input"))
      (node (ref "MOT2") (pin "1") (pinfunction "P_1") (pintype "passive"))
      (node (ref "R30") (pin "2") (pinfunction "2_2") (pintype "passive"))
    )
    (net (code "65") (name "SENS_MOTR1") (class "Default")
      (node (ref "IC6") (pin "3") (pinfunction "V3_3") (pintype "input"))
      (node (ref "IC7") (pin "3") (pinfunction "OUT1_3") (pintype "output"))
      (node (ref "R32") (pin "1") (pinfunction "1_1") (pintype "passive"))
    )
    (net (code "66") (name "SENS_MOTR2") (class "Default")
      (node (ref "IC6") (pin "4") (pinfunction "V4_4") (pintype "input"))
      (node (ref "MOT4") (pin "1") (pinfunction "P_1") (pintype "passive"))
      (node (ref "R32") (pin "2") (pinfunction "2_2") (pintype "passive"))
    )
    (net (code "67") (name "SRXD") (class "Default")
      (node (ref "CON_PROG") (pin "11") (pinfunction "11_11") (pintype "bidirectional"))
      (node (ref "IC1") (pin "23") (pinfunction "PC0(ADC0/PCINT8)_23") (pintype "bidirectional"))
    )
    (net (code "68") (name "STXD") (class "Default")
      (node (ref "CON_PROG") (pin "10") (pinfunction "10_10") (pintype "bidirectional"))
      (node (ref "IC1") (pin "24") (pinfunction "PC1(ADC1/PCINT9)_24") (pintype "bidirectional"))
    )
    (net (code "69") (name "TXD") (class "Default")
      (node (ref "IC1") (pin "31") (pinfunction "PD1(TXD/PCINT17)_31") (pintype "bidirectional"))
      (node (ref "IC3") (pin "2") (pinfunction "TXD_2") (pintype "bidirectional"))
    )
    (net (code "70") (name "TXIR") (class "Default")
      (node (ref "IC3") (pin "7") (pinfunction "IR_TXD_7") (pintype "bidirectional"))
      (node (ref "IC4") (pin "2") (pinfunction "TXD_2") (pintype "input"))
    )
    (net (code "71") (name "VCC") (class "Default")
      (node (ref "C1") (pin "1") (pinfunction "1_1") (pintype "passive"))
      (node (ref "C5") (pin "1") (pinfunction "1_1") (pintype "passive"))
      (node (ref "CON_PROG") (pin "1") (pinfunction "1_1") (pintype "bidirectional"))
      (node (ref "D1") (pin "C") (pinfunction "C_C") (pintype "passive"))
      (node (ref "D2") (pin "C") (pinfunction "C_C") (pintype "passive"))
      (node (ref "IC1") (pin "18") (pinfunction "AVCC_18") (pintype "passive"))
      (node (ref "IC1") (pin "4") (pinfunction "VCC_4") (pintype "power_in"))
      (node (ref "IC1") (pin "6") (pinfunction "VCC_6") (pintype "power_in"))
      (node (ref "IC2") (pin "3") (pinfunction "VCC_3") (pintype "bidirectional"))
      (node (ref "IC3") (pin "8") (pinfunction "VCC_8") (pintype "bidirectional"))
      (node (ref "IC4") (pin "5") (pinfunction "VCC_5") (pintype "power_in"))
      (node (ref "IC5") (pin "4") (pinfunction "VCC_4") (pintype "power_in"))
      (node (ref "IC6") (pin "10") (pinfunction "VCC_10") (pintype "power_in"))
      (node (ref "IC7") (pin "4") (pinfunction "VCC_4") (pintype "power_in"))
      (node (ref "IC7") (pin "7") (pinfunction "A0_7") (pintype "input"))
      (node (ref "IC8") (pin "10") (pinfunction "VCC_10") (pintype "power_in"))
      (node (ref "IC8") (pin "8") (pinfunction "ADR0_8") (pintype "input"))
      (node (ref "Q1") (pin "4") (pinfunction "VCC_4") (pintype "power_in"))
      (node (ref "Q5") (pin "C") (pinfunction "C_C") (pintype "passive"))
      (node (ref "Q6") (pin "C") (pinfunction "C_C") (pintype "passive"))
      (node (ref "Q7") (pin "C") (pinfunction "C_C") (pintype "passive"))
      (node (ref "Q8") (pin "C") (pinfunction "C_C") (pintype "passive"))
      (node (ref "R1") (pin "1") (pinfunction "1_1") (pintype "passive"))
      (node (ref "R10") (pin "1") (pinfunction "1_1") (pintype "passive"))
      (node (ref "R2") (pin "1") (pinfunction "1_1") (pintype "passive"))
      (node (ref "R33") (pin "2") (pinfunction "2_2") (pintype "passive"))
      (node (ref "R34") (pin "2") (pinfunction "2_2") (pintype "passive"))
      (node (ref "R35") (pin "2") (pinfunction "2_2") (pintype "passive"))
      (node (ref "R4") (pin "1") (pinfunction "1_1") (pintype "passive"))
      (node (ref "R5") (pin "1") (pinfunction "1_1") (pintype "passive"))
      (node (ref "R7") (pin "2") (pinfunction "2_2") (pintype "passive"))
      (node (ref "R8") (pin "2") (pinfunction "2_2") (pintype "passive"))
    )
    (net (code "72") (name "unconnected-(IC2-SC1-Pad8)") (class "Default")
      (node (ref "IC2") (pin "8") (pinfunction "SC1_8") (pintype "bidirectional"))
    )
    (net (code "73") (name "unconnected-(IC2-SD1-Pad7)") (class "Default")
      (node (ref "IC2") (pin "7") (pinfunction "SD1_7") (pintype "bidirectional"))
    )
    (net (code "74") (name "unconnected-(IC5-FAULTN-Pad6)") (class "Default")
      (node (ref "IC5") (pin "6") (pinfunction "FAULTN_6") (pintype "output"))
    )
    (net (code "75") (name "unconnected-(IC7-FAULTN-Pad6)") (class "Default")
      (node (ref "IC7") (pin "6") (pinfunction "FAULTN_6") (pintype "output"))
    )
  )
)
